# gps.net
KiCad netlist of a schematic drawn in EAGLE
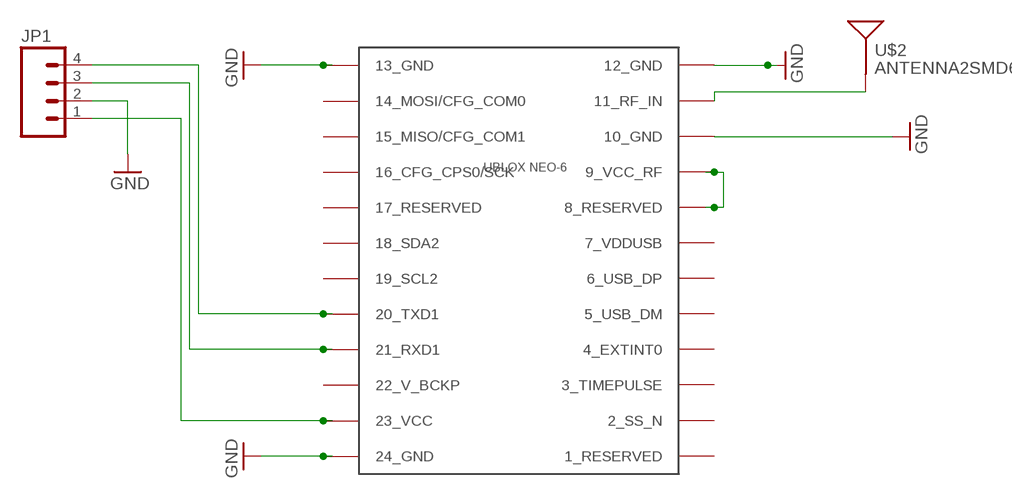
[diagram p0: schematic, sheet 1]

(export (version "E")
  (design (tool "Eeschema 10.0.6"))
  (components
    (comp (ref "JP1")
      (value "M04LOCK_LONGPADS")
      (footprint "eagle-import:1X04_LOCK_LONGPADS")
      (libsource (lib "eagle-import") (part "M04LOCK_LONGPADS"))
    )
    (comp (ref "U$1")
      (value "UBLOX_NEO-6")
      (footprint "eagle-import:UBLOX_NEO-6P")
      (libsource (lib "eagle-import") (part "UBLOX_NEO-6"))
    )
    (comp (ref "U$2")
      (value "ANTENNA2SMD6")
      (footprint "eagle-import:ANTENNA-CHIP6")
      (libsource (lib "eagle-import") (part "ANTENNA2SMD6"))
    )
  )
  (nets
    (net (code "1") (name "GND") (class "Default")
      (node (ref "JP1") (pin "2") (pinfunction "2_2") (pintype "passive"))
      (node (ref "U$1") (pin "10_GND") (pinfunction "10_GND_10_GND") (pintype "bidirectional"))
      (node (ref "U$1") (pin "12_GND") (pinfunction "12_GND_12_GND") (pintype "bidirectional"))
      (node (ref "U$1") (pin "13_GND") (pinfunction "13_GND_13_GND") (pintype "bidirectional"))
      (node (ref "U$1") (pin "24_GND") (pinfunction "24_GND_24_GND") (pintype "bidirectional"))
    )
    (net (code "2") (name "Net-(JP1-Pad1)") (class "Default")
      (node (ref "JP1") (pin "1") (pinfunction "1_1") (pintype "passive"))
      (node (ref "U$1") (pin "23_VCC") (pinfunction "23_VCC_23_VCC") (pintype "bidirectional"))
    )
    (net (code "3") (name "Net-(JP1-Pad3)") (class "Default")
      (node (ref "JP1") (pin "3") (pinfunction "3_3") (pintype "passive"))
      (node (ref "U$1") (pin "21_RXD1") (pinfunction "21_RXD1_21_RXD1") (pintype "bidirectional"))
    )
    (net (code "4") (name "Net-(JP1-Pad4)") (class "Default")
      (node (ref "JP1") (pin "4") (pinfunction "4_4") (pintype "passive"))
      (node (ref "U$1") (pin "20_TXD1") (pinfunction "20_TXD1_20_TXD1") (pintype "bidirectional"))
    )
    (net (code "5") (name "Net-(U$1-Pad8_RESERVED)") (class "Default")
      (node (ref "U$1") (pin "8_RESERVED") (pinfunction "8_RESERVED_8_RESERVED") (pintype "bidirectional"))
      (node (ref "U$1") (pin "9_VCC_RF") (pinfunction "9_VCC_RF_9_VCC_RF") (pintype "bidirectional"))
    )
    (net (code "6") (name "Net-(U$2-SIGNAL)") (class "Default")
      (node (ref "U$1") (pin "11_RF_IN") (pinfunction "11_RF_IN_11_RF_IN") (pintype "bidirectional"))
      (node (ref "U$2") (pin "1") (pinfunction "SIGNAL_1") (pintype "bidirectional"))
    )
    (net (code "7") (name "unconnected-(U$1-Pad1_RESERVED)") (class "Default")
      (node (ref "U$1") (pin "1_RESERVED") (pinfunction "1_RESERVED_1_RESERVED") (pintype "bidirectional"))
    )
    (net (code "8") (name "unconnected-(U$1-Pad2_SS_N)") (class "Default")
      (node (ref "U$1") (pin "2_SS_N") (pinfunction "2_SS_N_2_SS_N") (pintype "bidirectional"))
    )
    (net (code "9") (name "unconnected-(U$1-Pad3_TIMEPULSE)") (class "Default")
      (node (ref "U$1") (pin "3_TIMEPULSE") (pinfunction "3_TIMEPULSE_3_TIMEPULSE") (pintype "bidirectional"))
    )
    (net (code "10") (name "unconnected-(U$1-Pad4_EXTINT0)") (class "Default")
      (node (ref "U$1") (pin "4_EXTINT0") (pinfunction "4_EXTINT0_4_EXTINT0") (pintype "bidirectional"))
    )
    (net (code "11") (name "unconnected-(U$1-Pad5_USB_DM)") (class "Default")
      (node (ref "U$1") (pin "5_USB_DM") (pinfunction "5_USB_DM_5_USB_DM") (pintype "bidirectional"))
    )
    (net (code "12") (name "unconnected-(U$1-Pad6_USB_DP)") (class "Default")
      (node (ref "U$1") (pin "6_USB_DP") (pinfunction "6_USB_DP_6_USB_DP") (pintype "bidirectional"))
    )
    (net (code "13") (name "unconnected-(U$1-Pad7_VDDUSB)") (class "Default")
      (node (ref "U$1") (pin "7_VDDUSB") (pinfunction "7_VDDUSB_7_VDDUSB") (pintype "bidirectional"))
    )
    (net (code "14") (name "unconnected-(U$1-Pad14_MOSI{slash}CFG_COM0)") (class "Default")
      (node (ref "U$1") (pin "14_MOSI/CFG_COM0") (pinfunction "14_MOSI/CFG_COM0_14_MOSI/CFG_COM0") (pintype "bidirectional"))
    )
    (net (code "15") (name "unconnected-(U$1-Pad15_MISO{slash}CFG_COM1)") (class "Default")
      (node (ref "U$1") (pin "15_MISO/CFG_COM1") (pinfunction "15_MISO/CFG_COM1_15_MISO/CFG_COM1") (pintype "bidirectional"))
    )
    (net (code "16") (name "unconnected-(U$1-Pad16_CFG_CPS0{slash}SCK)") (class "Default")
      (node (ref "U$1") (pin "16_CFG_CPS0/SCK") (pinfunction "16_CFG_CPS0/SCK_16_CFG_CPS0/SCK") (pintype "bidirectional"))
    )
    (net (code "17") (name "unconnected-(U$1-Pad17_RESERVED)") (class "Default")
      (node (ref "U$1") (pin "17_RESERVED") (pinfunction "17_RESERVED_17_RESERVED") (pintype "bidirectional"))
    )
    (net (code "18") (name "unconnected-(U$1-Pad18_SDA2)") (class "Default")
      (node (ref "U$1") (pin "18_SDA2") (pinfunction "18_SDA2_18_SDA2") (pintype "bidirectional"))
    )
    (net (code "19") (name "unconnected-(U$1-Pad19_SCL2)") (class "Default")
      (node (ref "U$1") (pin "19_SCL2") (pinfunction "19_SCL2_19_SCL2") (pintype "bidirectional"))
    )
    (net (code "20") (name "unconnected-(U$1-Pad22_V_BCKP)") (class "Default")
      (node (ref "U$1") (pin "22_V_BCKP") (pinfunction "22_V_BCKP_22_V_BCKP") (pintype "bidirectional"))
    )
  )
)
